# 17_-FPGA_Power_Supply.net
KiCad netlist of a schematic drawn in Altium Designer
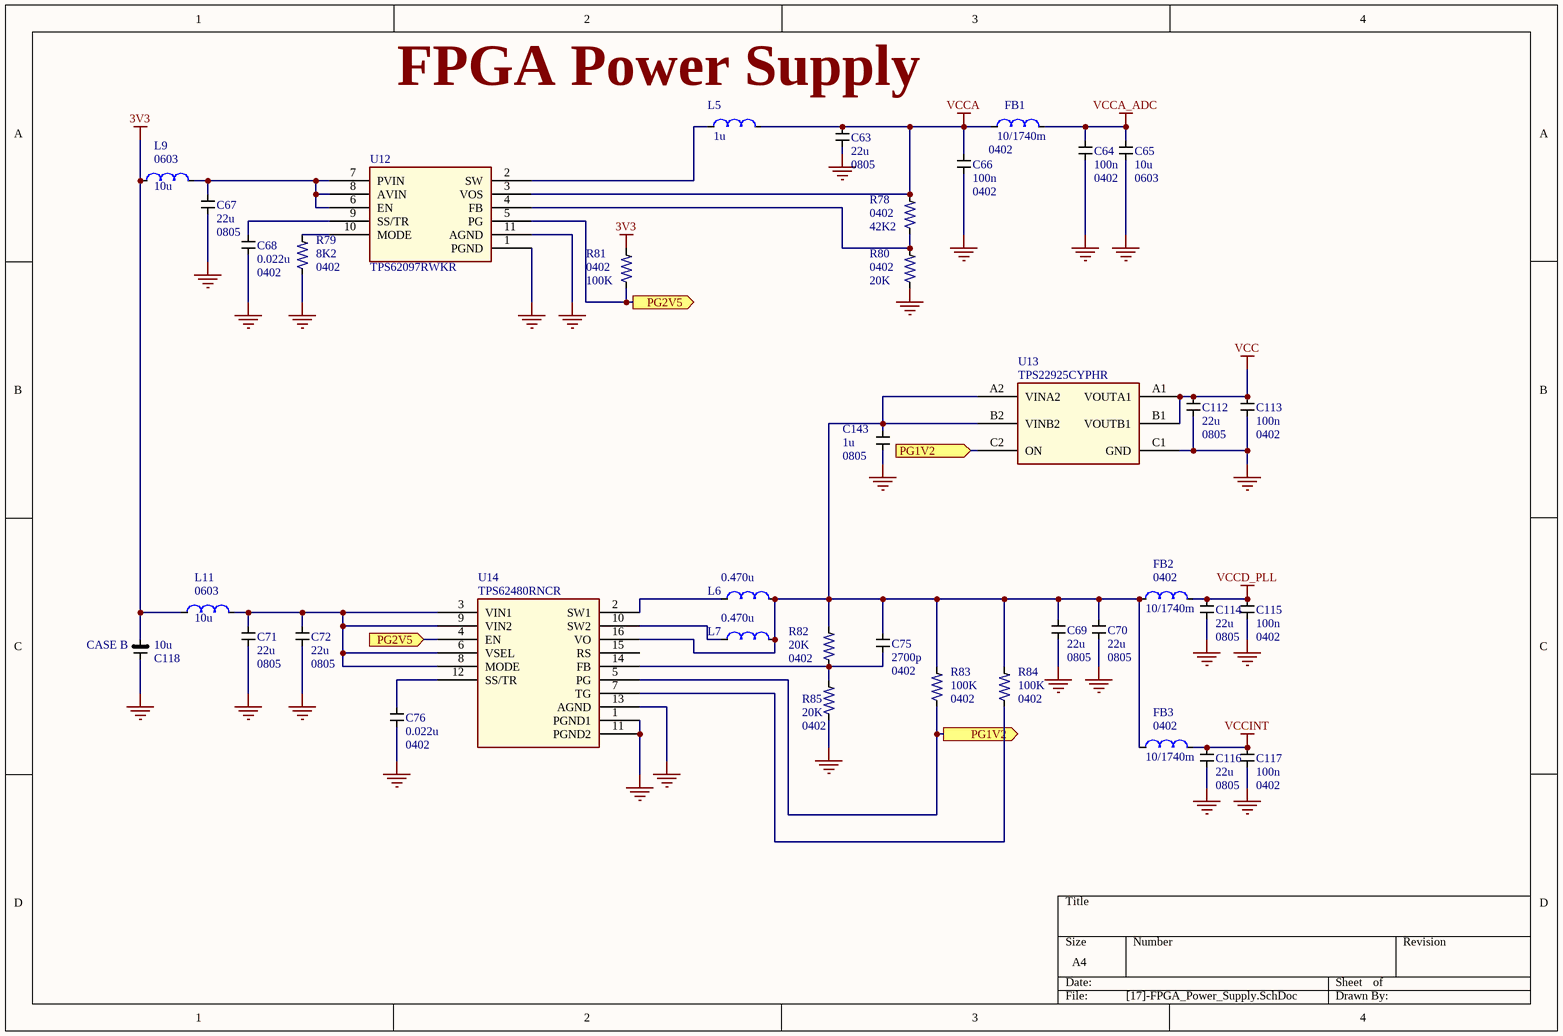
[diagram p0: [17]-FPGA_Power_Supply.SchDoc]

(export (version "E")
  (design (tool "Eeschema 10.0.6"))
  (components
    (comp (ref "C63")
      (value "22u")
      (footprint "*CAPC2013X140N")
      (fields (field (name "PCB PACKAGE") "0805"))
      (libsource (lib "08053D475KAT2A") (part "Component_1"))
    )
    (comp (ref "C64")
      (value "100n")
      (footprint "*CAPC1005X60N")
      (fields (field (name "PCB STAKE") "0402"))
      (libsource (lib "04023C104KAT2A_0402") (part "Component_1"))
    )
    (comp (ref "C65")
      (value "10u")
      (fields (field (name "PCB FOOTPRINT") "0603"))
      (libsource (lib "06031C104KAT2A") (part "Component_1"))
    )
    (comp (ref "C66")
      (value "100n")
      (footprint "*CAPC1005X60N")
      (fields (field (name "PCB STAKE") "0402"))
      (libsource (lib "04023C104KAT2A_0402") (part "Component_1"))
    )
    (comp (ref "C67")
      (value "22u")
      (footprint "*CAPC2013X140N")
      (fields (field (name "PCB PACKAGE") "0805"))
      (libsource (lib "08053D475KAT2A") (part "Component_1"))
    )
    (comp (ref "C68")
      (value "0.022u")
      (footprint "*CAPC1005X60N")
      (fields (field (name "PCB STAKE") "0402"))
      (libsource (lib "04023C104KAT2A_0402") (part "Component_1"))
    )
    (comp (ref "C69")
      (value "22u")
      (footprint "*CAPC2013X140N")
      (fields (field (name "PCB PACKAGE") "0805"))
      (libsource (lib "08053D475KAT2A") (part "Component_1"))
    )
    (comp (ref "C70")
      (value "22u")
      (footprint "*CAPC2013X140N")
      (fields (field (name "PCB PACKAGE") "0805"))
      (libsource (lib "08053D475KAT2A") (part "Component_1"))
    )
    (comp (ref "C71")
      (value "22u")
      (footprint "*CAPC2013X140N")
      (fields (field (name "PCB PACKAGE") "0805"))
      (libsource (lib "08053D475KAT2A") (part "Component_1"))
    )
    (comp (ref "C72")
      (value "22u")
      (footprint "*CAPC2013X140N")
      (fields (field (name "PCB PACKAGE") "0805"))
      (libsource (lib "08053D475KAT2A") (part "Component_1"))
    )
    (comp (ref "C75")
      (value "2700p")
      (footprint "*CAPC1005X60N")
      (fields (field (name "PCB STAKE") "0402"))
      (libsource (lib "04023C104KAT2A_0402") (part "Component_1"))
    )
    (comp (ref "C76")
      (value "0.022u")
      (footprint "*CAPC1005X60N")
      (fields (field (name "PCB STAKE") "0402"))
      (libsource (lib "04023C104KAT2A_0402") (part "Component_1"))
    )
    (comp (ref "C112")
      (value "22u")
      (footprint "*CAPC2013X140N")
      (fields (field (name "PCB PACKAGE") "0805"))
      (libsource (lib "08053D475KAT2A") (part "Component_1"))
    )
    (comp (ref "C113")
      (value "100n")
      (footprint "*CAPC1005X60N")
      (fields (field (name "PCB STAKE") "0402"))
      (libsource (lib "04023C104KAT2A_0402") (part "Component_1"))
    )
    (comp (ref "C114")
      (value "22u")
      (footprint "*CAPC2013X140N")
      (fields (field (name "PCB PACKAGE") "0805"))
      (libsource (lib "08053D475KAT2A") (part "Component_1"))
    )
    (comp (ref "C115")
      (value "100n")
      (footprint "*CAPC1005X60N")
      (fields (field (name "PCB STAKE") "0402"))
      (libsource (lib "04023C104KAT2A_0402") (part "Component_1"))
    )
    (comp (ref "C116")
      (value "22u")
      (footprint "*CAPC2013X140N")
      (fields (field (name "PCB PACKAGE") "0805"))
      (libsource (lib "08053D475KAT2A") (part "Component_1"))
    )
    (comp (ref "C117")
      (value "100n")
      (footprint "*CAPC1005X60N")
      (fields (field (name "PCB STAKE") "0402"))
      (libsource (lib "04023C104KAT2A_0402") (part "Component_1"))
    )
    (comp (ref "C118")
      (value "10u")
      (footprint "CAPC3529X21N")
      (fields (field (name "CASE") "CASE B"))
      (libsource (lib "TAJB107K006TNJ") (part "Component_1"))
    )
    (comp (ref "C143")
      (value "1u")
      (fields (field (name "PCB FOOTPRINT") "0805"))
      (libsource (lib "06031C104KAT2A") (part "Component_1"))
    )
    (comp (ref "FB1")
      (value "10/1740m")
      (footprint "*CAPC1005X55N")
      (fields (field (name "PACKAGE TYPE") "0402"))
      (libsource (lib "CAPC1005X55N") (part "Component_1"))
    )
    (comp (ref "FB2")
      (value "10/1740m")
      (footprint "*CAPC1005X55N")
      (fields (field (name "PACKAGE TYPE") "0402"))
      (libsource (lib "CAPC1005X55N") (part "Component_1"))
    )
    (comp (ref "FB3")
      (value "10/1740m")
      (footprint "*CAPC1005X55N")
      (fields (field (name "PACKAGE TYPE") "0402"))
      (libsource (lib "CAPC1005X55N") (part "Component_1"))
    )
    (comp (ref "L5")
      (value "1u")
      (footprint "*INDM4040X210")
      (libsource (lib "XFL4020-102MEC") (part "Component_1"))
    )
    (comp (ref "L6")
      (value "0.470u")
      (footprint "INDC3234X16N")
      (libsource (lib "XFL4015-471MEC") (part "Component_1"))
    )
    (comp (ref "L7")
      (value "0.470u")
      (footprint "INDC3234X16N")
      (libsource (lib "XFL4015-471MEC") (part "Component_1"))
    )
    (comp (ref "L9")
      (value "10u")
      (footprint "*INDC1608X95N")
      (fields (field (name "PCB LAYOUT:") "0603"))
      (libsource (lib "MLZ1608M100WTD25") (part "Component_1"))
    )
    (comp (ref "L11")
      (value "10u")
      (footprint "*INDC1608X95N")
      (fields (field (name "PCB LAYOUT:") "0603"))
      (libsource (lib "MLZ1608M100WTD25") (part "Component_1"))
    )
    (comp (ref "R78")
      (value "42K2")
      (footprint "*R0402")
      (description "Res Thin Film 0603 76.8 Ohm 0.1% 1/10W Â±15ppm/Â°C Molded SMD Paper T/R")
      (fields (field (name "PCB FOOTPRINT") "0402"))
      (libsource (lib "SMD-RES-100K-1_-1_16W_0402_") (part "RP73D1J76R8BTDG"))
    )
    (comp (ref "R79")
      (value "8K2")
      (footprint "*R0402")
      (description "Res Thin Film 0603 76.8 Ohm 0.1% 1/10W Â±15ppm/Â°C Molded SMD Paper T/R")
      (fields (field (name "PCB FOOTPRINT") "0402"))
      (libsource (lib "SMD-RES-100K-1_-1_16W_0402_") (part "RP73D1J76R8BTDG"))
    )
    (comp (ref "R80")
      (value "20K")
      (footprint "*R0402")
      (description "Res Thin Film 0603 76.8 Ohm 0.1% 1/10W Â±15ppm/Â°C Molded SMD Paper T/R")
      (fields (field (name "PCB FOOTPRINT") "0402"))
      (libsource (lib "SMD-RES-100K-1_-1_16W_0402_") (part "RP73D1J76R8BTDG"))
    )
    (comp (ref "R81")
      (value "100K")
      (footprint "*R0402")
      (description "Res Thin Film 0603 76.8 Ohm 0.1% 1/10W Â±15ppm/Â°C Molded SMD Paper T/R")
      (fields (field (name "PCB FOOTPRINT") "0402"))
      (libsource (lib "SMD-RES-100K-1_-1_16W_0402_") (part "RP73D1J76R8BTDG"))
    )
    (comp (ref "R82")
      (value "20K")
      (footprint "*R0402")
      (description "Res Thin Film 0603 76.8 Ohm 0.1% 1/10W Â±15ppm/Â°C Molded SMD Paper T/R")
      (fields (field (name "PCB FOOTPRINT") "0402"))
      (libsource (lib "SMD-RES-100K-1_-1_16W_0402_") (part "RP73D1J76R8BTDG"))
    )
    (comp (ref "R83")
      (value "100K")
      (footprint "*R0402")
      (description "Res Thin Film 0603 76.8 Ohm 0.1% 1/10W Â±15ppm/Â°C Molded SMD Paper T/R")
      (fields (field (name "PCB FOOTPRINT") "0402"))
      (libsource (lib "SMD-RES-100K-1_-1_16W_0402_") (part "RP73D1J76R8BTDG"))
    )
    (comp (ref "R84")
      (value "100K")
      (footprint "*R0402")
      (description "Res Thin Film 0603 76.8 Ohm 0.1% 1/10W Â±15ppm/Â°C Molded SMD Paper T/R")
      (fields (field (name "PCB FOOTPRINT") "0402"))
      (libsource (lib "SMD-RES-100K-1_-1_16W_0402_") (part "RP73D1J76R8BTDG"))
    )
    (comp (ref "R85")
      (value "20K")
      (footprint "*R0402")
      (description "Res Thin Film 0603 76.8 Ohm 0.1% 1/10W Â±15ppm/Â°C Molded SMD Paper T/R")
      (fields (field (name "PCB FOOTPRINT") "0402"))
      (libsource (lib "SMD-RES-100K-1_-1_16W_0402_") (part "RP73D1J76R8BTDG"))
    )
    (comp (ref "U12")
      (value "TPS62097RWKR")
      (footprint "PCBComponent_1 - duplicate1")
      (libsource (lib "TPS62097RWKR") (part "Component_1"))
    )
    (comp (ref "U13")
      (value "TPS22925CYPHR")
      (footprint "BGA")
      (libsource (lib "TPS22925CYPHR") (part "Component_1"))
    )
    (comp (ref "U14")
      (value "TPS62480RNCR")
      (footprint "PCBComponent_1")
      (libsource (lib "TPS62480RNCR") (part "Component_1"))
    )
  )
  (nets
    (net (code "1") (name "/PG1V2") (class "Default")
      (node (ref "R83") (pin "1") (pinfunction "1_1") (pintype "passive"))
      (node (ref "U13") (pin "C2") (pinfunction "ON_C2") (pintype "passive"))
      (node (ref "U14") (pin "5") (pinfunction "PG_5") (pintype "passive"))
    )
    (net (code "2") (name "/PG2V5") (class "Default")
      (node (ref "R81") (pin "1") (pinfunction "1_1") (pintype "passive"))
      (node (ref "U12") (pin "5") (pinfunction "PG_5") (pintype "passive"))
      (node (ref "U14") (pin "4") (pinfunction "EN_4") (pintype "passive"))
    )
    (net (code "3") (name "3V3") (class "Default")
      (node (ref "C118") (pin "1") (pinfunction "1_1") (pintype "passive"))
      (node (ref "L11") (pin "1") (pinfunction "1_1") (pintype "passive"))
      (node (ref "L9") (pin "1") (pinfunction "1_1") (pintype "passive"))
      (node (ref "R81") (pin "2") (pinfunction "2_2") (pintype "passive"))
    )
    (net (code "4") (name "GND") (class "Default")
      (node (ref "C112") (pin "1") (pinfunction "1_1") (pintype "passive"))
      (node (ref "C113") (pin "1") (pinfunction "1_1") (pintype "passive"))
      (node (ref "C114") (pin "1") (pinfunction "1_1") (pintype "passive"))
      (node (ref "C115") (pin "1") (pinfunction "1_1") (pintype "passive"))
      (node (ref "C116") (pin "1") (pinfunction "1_1") (pintype "passive"))
      (node (ref "C117") (pin "1") (pinfunction "1_1") (pintype "passive"))
      (node (ref "C118") (pin "2") (pinfunction "2_2") (pintype "passive"))
      (node (ref "C143") (pin "1") (pinfunction "1_1") (pintype "passive"))
      (node (ref "C63") (pin "1") (pinfunction "1_1") (pintype "passive"))
      (node (ref "C64") (pin "1") (pinfunction "1_1") (pintype "passive"))
      (node (ref "C65") (pin "1") (pinfunction "1_1") (pintype "passive"))
      (node (ref "C66") (pin "1") (pinfunction "1_1") (pintype "passive"))
      (node (ref "C67") (pin "1") (pinfunction "1_1") (pintype "passive"))
      (node (ref "C68") (pin "1") (pinfunction "1_1") (pintype "passive"))
      (node (ref "C69") (pin "1") (pinfunction "1_1") (pintype "passive"))
      (node (ref "C70") (pin "1") (pinfunction "1_1") (pintype "passive"))
      (node (ref "C71") (pin "1") (pinfunction "1_1") (pintype "passive"))
      (node (ref "C72") (pin "1") (pinfunction "1_1") (pintype "passive"))
      (node (ref "C76") (pin "1") (pinfunction "1_1") (pintype "passive"))
      (node (ref "R79") (pin "1") (pinfunction "1_1") (pintype "passive"))
      (node (ref "R80") (pin "1") (pinfunction "1_1") (pintype "passive"))
      (node (ref "R85") (pin "1") (pinfunction "1_1") (pintype "passive"))
      (node (ref "U12") (pin "1") (pinfunction "PGND_1") (pintype "passive"))
      (node (ref "U12") (pin "11") (pinfunction "AGND_11") (pintype "passive"))
      (node (ref "U13") (pin "C1") (pinfunction "GND_C1") (pintype "power_in"))
      (node (ref "U14") (pin "1") (pinfunction "PGND1_1") (pintype "passive"))
      (node (ref "U14") (pin "11") (pinfunction "PGND2_11") (pintype "passive"))
      (node (ref "U14") (pin "13") (pinfunction "AGND_13") (pintype "passive"))
    )
    (net (code "5") (name "Net-(U12-AVIN)") (class "Default")
      (node (ref "C67") (pin "2") (pinfunction "2_2") (pintype "passive"))
      (node (ref "L9") (pin "2") (pinfunction "2_2") (pintype "passive"))
      (node (ref "U12") (pin "6") (pinfunction "EN_6") (pintype "passive"))
      (node (ref "U12") (pin "7") (pinfunction "PVIN_7") (pintype "passive"))
      (node (ref "U12") (pin "8") (pinfunction "AVIN_8") (pintype "passive"))
    )
    (net (code "6") (name "Net-(U12-FB)") (class "Default")
      (node (ref "R78") (pin "1") (pinfunction "1_1") (pintype "passive"))
      (node (ref "R80") (pin "2") (pinfunction "2_2") (pintype "passive"))
      (node (ref "U12") (pin "4") (pinfunction "FB_4") (pintype "passive"))
    )
    (net (code "7") (name "Net-(U12-MODE)") (class "Default")
      (node (ref "R79") (pin "2") (pinfunction "2_2") (pintype "passive"))
      (node (ref "U12") (pin "10") (pinfunction "MODE_10") (pintype "passive"))
    )
    (net (code "8") (name "Net-(U12-SS{slash}TR)") (class "Default")
      (node (ref "C68") (pin "2") (pinfunction "2_2") (pintype "passive"))
      (node (ref "U12") (pin "9") (pinfunction "SS/TR_9") (pintype "passive"))
    )
    (net (code "9") (name "Net-(U12-SW)") (class "Default")
      (node (ref "L5") (pin "1") (pinfunction "1_1") (pintype "passive"))
      (node (ref "U12") (pin "2") (pinfunction "SW_2") (pintype "passive"))
    )
    (net (code "10") (name "Net-(U13-VINA2)") (class "Default")
      (node (ref "C143") (pin "2") (pinfunction "2_2") (pintype "passive"))
      (node (ref "C69") (pin "2") (pinfunction "2_2") (pintype "passive"))
      (node (ref "C70") (pin "2") (pinfunction "2_2") (pintype "passive"))
      (node (ref "C75") (pin "2") (pinfunction "2_2") (pintype "passive"))
      (node (ref "FB2") (pin "1") (pinfunction "1_1") (pintype "passive"))
      (node (ref "FB3") (pin "1") (pinfunction "1_1") (pintype "passive"))
      (node (ref "L6") (pin "2") (pinfunction "2_2") (pintype "passive"))
      (node (ref "L7") (pin "2") (pinfunction "2_2") (pintype "passive"))
      (node (ref "R82") (pin "2") (pinfunction "2_2") (pintype "passive"))
      (node (ref "R83") (pin "2") (pinfunction "2_2") (pintype "passive"))
      (node (ref "R84") (pin "2") (pinfunction "2_2") (pintype "passive"))
      (node (ref "U13") (pin "A2") (pinfunction "VINA2_A2") (pintype "power_in"))
      (node (ref "U13") (pin "B2") (pinfunction "VINB2_B2") (pintype "power_in"))
      (node (ref "U14") (pin "16") (pinfunction "VO_16") (pintype "passive"))
    )
    (net (code "11") (name "Net-(U14-FB)") (class "Default")
      (node (ref "C75") (pin "1") (pinfunction "1_1") (pintype "passive"))
      (node (ref "R82") (pin "1") (pinfunction "1_1") (pintype "passive"))
      (node (ref "R85") (pin "2") (pinfunction "2_2") (pintype "passive"))
      (node (ref "U14") (pin "14") (pinfunction "FB_14") (pintype "passive"))
    )
    (net (code "12") (name "Net-(U14-MODE)") (class "Default")
      (node (ref "C71") (pin "2") (pinfunction "2_2") (pintype "passive"))
      (node (ref "C72") (pin "2") (pinfunction "2_2") (pintype "passive"))
      (node (ref "L11") (pin "2") (pinfunction "2_2") (pintype "passive"))
      (node (ref "U14") (pin "3") (pinfunction "VIN1_3") (pintype "passive"))
      (node (ref "U14") (pin "6") (pinfunction "VSEL_6") (pintype "passive"))
      (node (ref "U14") (pin "8") (pinfunction "MODE_8") (pintype "passive"))
      (node (ref "U14") (pin "9") (pinfunction "VIN2_9") (pintype "passive"))
    )
    (net (code "13") (name "Net-(U14-SS{slash}TR)") (class "Default")
      (node (ref "C76") (pin "2") (pinfunction "2_2") (pintype "passive"))
      (node (ref "U14") (pin "12") (pinfunction "SS/TR_12") (pintype "passive"))
    )
    (net (code "14") (name "Net-(U14-SW1)") (class "Default")
      (node (ref "L6") (pin "1") (pinfunction "1_1") (pintype "passive"))
      (node (ref "U14") (pin "2") (pinfunction "SW1_2") (pintype "passive"))
    )
    (net (code "15") (name "Net-(U14-SW2)") (class "Default")
      (node (ref "L7") (pin "1") (pinfunction "1_1") (pintype "passive"))
      (node (ref "U14") (pin "10") (pinfunction "SW2_10") (pintype "passive"))
    )
    (net (code "16") (name "Net-(U14-TG)") (class "Default")
      (node (ref "R84") (pin "1") (pinfunction "1_1") (pintype "passive"))
      (node (ref "U14") (pin "7") (pinfunction "TG_7") (pintype "passive"))
    )
    (net (code "17") (name "VCC") (class "Default")
      (node (ref "C112") (pin "2") (pinfunction "2_2") (pintype "passive"))
      (node (ref "C113") (pin "2") (pinfunction "2_2") (pintype "passive"))
      (node (ref "U13") (pin "A1") (pinfunction "VOUTA1_A1") (pintype "power_in"))
      (node (ref "U13") (pin "B1") (pinfunction "VOUTB1_B1") (pintype "power_in"))
    )
    (net (code "18") (name "VCCA") (class "Default")
      (node (ref "C63") (pin "2") (pinfunction "2_2") (pintype "passive"))
      (node (ref "C66") (pin "2") (pinfunction "2_2") (pintype "passive"))
      (node (ref "FB1") (pin "1") (pinfunction "1_1") (pintype "passive"))
      (node (ref "L5") (pin "2") (pinfunction "2_2") (pintype "passive"))
      (node (ref "R78") (pin "2") (pinfunction "2_2") (pintype "passive"))
      (node (ref "U12") (pin "3") (pinfunction "VOS_3") (pintype "passive"))
    )
    (net (code "19") (name "VCCA_ADC") (class "Default")
      (node (ref "C64") (pin "2") (pinfunction "2_2") (pintype "passive"))
      (node (ref "C65") (pin "2") (pinfunction "2_2") (pintype "passive"))
      (node (ref "FB1") (pin "2") (pinfunction "2_2") (pintype "passive"))
    )
    (net (code "20") (name "VCCD_PLL") (class "Default")
      (node (ref "C114") (pin "2") (pinfunction "2_2") (pintype "passive"))
      (node (ref "C115") (pin "2") (pinfunction "2_2") (pintype "passive"))
      (node (ref "FB2") (pin "2") (pinfunction "2_2") (pintype "passive"))
    )
    (net (code "21") (name "VCCINT") (class "Default")
      (node (ref "C116") (pin "2") (pinfunction "2_2") (pintype "passive"))
      (node (ref "C117") (pin "2") (pinfunction "2_2") (pintype "passive"))
      (node (ref "FB3") (pin "2") (pinfunction "2_2") (pintype "passive"))
    )
    (net (code "22") (name "unconnected-(U14-RS-Pad15)") (class "Default")
      (node (ref "U14") (pin "15") (pinfunction "RS_15") (pintype "passive"))
    )
  )
)
